# round-epaper-demo.net
KiCad netlist of a schematic drawn in EAGLE
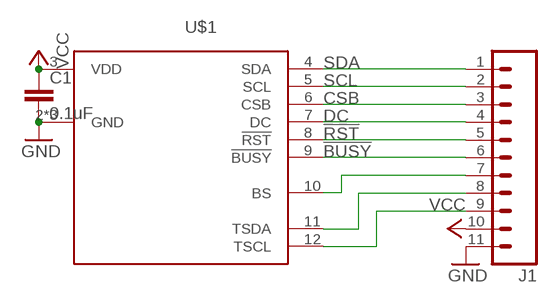
[diagram p0: schematic, sheet 1]

(export (version "E")
  (design (tool "Eeschema 10.0.6"))
  (components
    (comp (ref "C1")
      (value "0.1uF")
      (footprint "eagle-import:0603-CAP")
      (libsource (lib "eagle-import") (part "CAP0603-CAP"))
    )
    (comp (ref "J1")
      (value "M11PTH")
      (footprint "eagle-import:1X11")
      (libsource (lib "eagle-import") (part "M11PTH"))
    )
    (comp (ref "U$1")
      (value "GDEP011TT2")
      (footprint "eagle-import:FH26W-15S-0.3S")
      (libsource (lib "eagle-import") (part "GDEP011TT2"))
    )
  )
  (nets
    (net (code "1") (name "/CSB") (class "Default")
      (node (ref "J1") (pin "3") (pinfunction "3_3") (pintype "passive"))
      (node (ref "U$1") (pin "6") (pinfunction "CSB_6") (pintype "bidirectional"))
    )
    (net (code "2") (name "/DC") (class "Default")
      (node (ref "J1") (pin "4") (pinfunction "4_4") (pintype "passive"))
      (node (ref "U$1") (pin "7") (pinfunction "DC_7") (pintype "bidirectional"))
    )
    (net (code "3") (name "/SCL") (class "Default")
      (node (ref "J1") (pin "2") (pinfunction "2_2") (pintype "passive"))
      (node (ref "U$1") (pin "5") (pinfunction "SCL_5") (pintype "bidirectional"))
    )
    (net (code "4") (name "/SDA") (class "Default")
      (node (ref "J1") (pin "1") (pinfunction "1_1") (pintype "passive"))
      (node (ref "U$1") (pin "4") (pinfunction "SDA_4") (pintype "bidirectional"))
    )
    (net (code "5") (name "/~{BUSY}") (class "Default")
      (node (ref "J1") (pin "6") (pinfunction "6_6") (pintype "passive"))
      (node (ref "U$1") (pin "9") (pinfunction "~{BUSY}_9") (pintype "bidirectional"))
    )
    (net (code "6") (name "/~{RST}") (class "Default")
      (node (ref "J1") (pin "5") (pinfunction "5_5") (pintype "passive"))
      (node (ref "U$1") (pin "8") (pinfunction "~{RST}_8") (pintype "bidirectional"))
    )
    (net (code "7") (name "GND") (class "Default")
      (node (ref "C1") (pin "2") (pinfunction "2_2") (pintype "passive"))
      (node (ref "J1") (pin "11") (pinfunction "11_11") (pintype "passive"))
      (node (ref "U$1") (pin "2") (pinfunction "GND_2") (pintype "bidirectional"))
      (node (ref "U$1") (pin "EXP1") (pinfunction "GND_EXP1") (pintype "bidirectional"))
      (node (ref "U$1") (pin "EXP2") (pinfunction "GND_EXP2") (pintype "bidirectional"))
    )
    (net (code "8") (name "Net-(U$1-BS)") (class "Default")
      (node (ref "J1") (pin "7") (pinfunction "7_7") (pintype "passive"))
      (node (ref "U$1") (pin "10") (pinfunction "BS_10") (pintype "bidirectional"))
    )
    (net (code "9") (name "Net-(U$1-TSCL)") (class "Default")
      (node (ref "J1") (pin "9") (pinfunction "9_9") (pintype "passive"))
      (node (ref "U$1") (pin "12") (pinfunction "TSCL_12") (pintype "bidirectional"))
    )
    (net (code "10") (name "Net-(U$1-TSDA)") (class "Default")
      (node (ref "J1") (pin "8") (pinfunction "8_8") (pintype "passive"))
      (node (ref "U$1") (pin "11") (pinfunction "TSDA_11") (pintype "bidirectional"))
    )
    (net (code "11") (name "VCC") (class "Default")
      (node (ref "C1") (pin "1") (pinfunction "1_1") (pintype "passive"))
      (node (ref "J1") (pin "10") (pinfunction "10_10") (pintype "passive"))
      (node (ref "U$1") (pin "3") (pinfunction "VDD_3") (pintype "bidirectional"))
    )
  )
)
